# ThermoBase.net
KiCad netlist of a schematic drawn in EAGLE
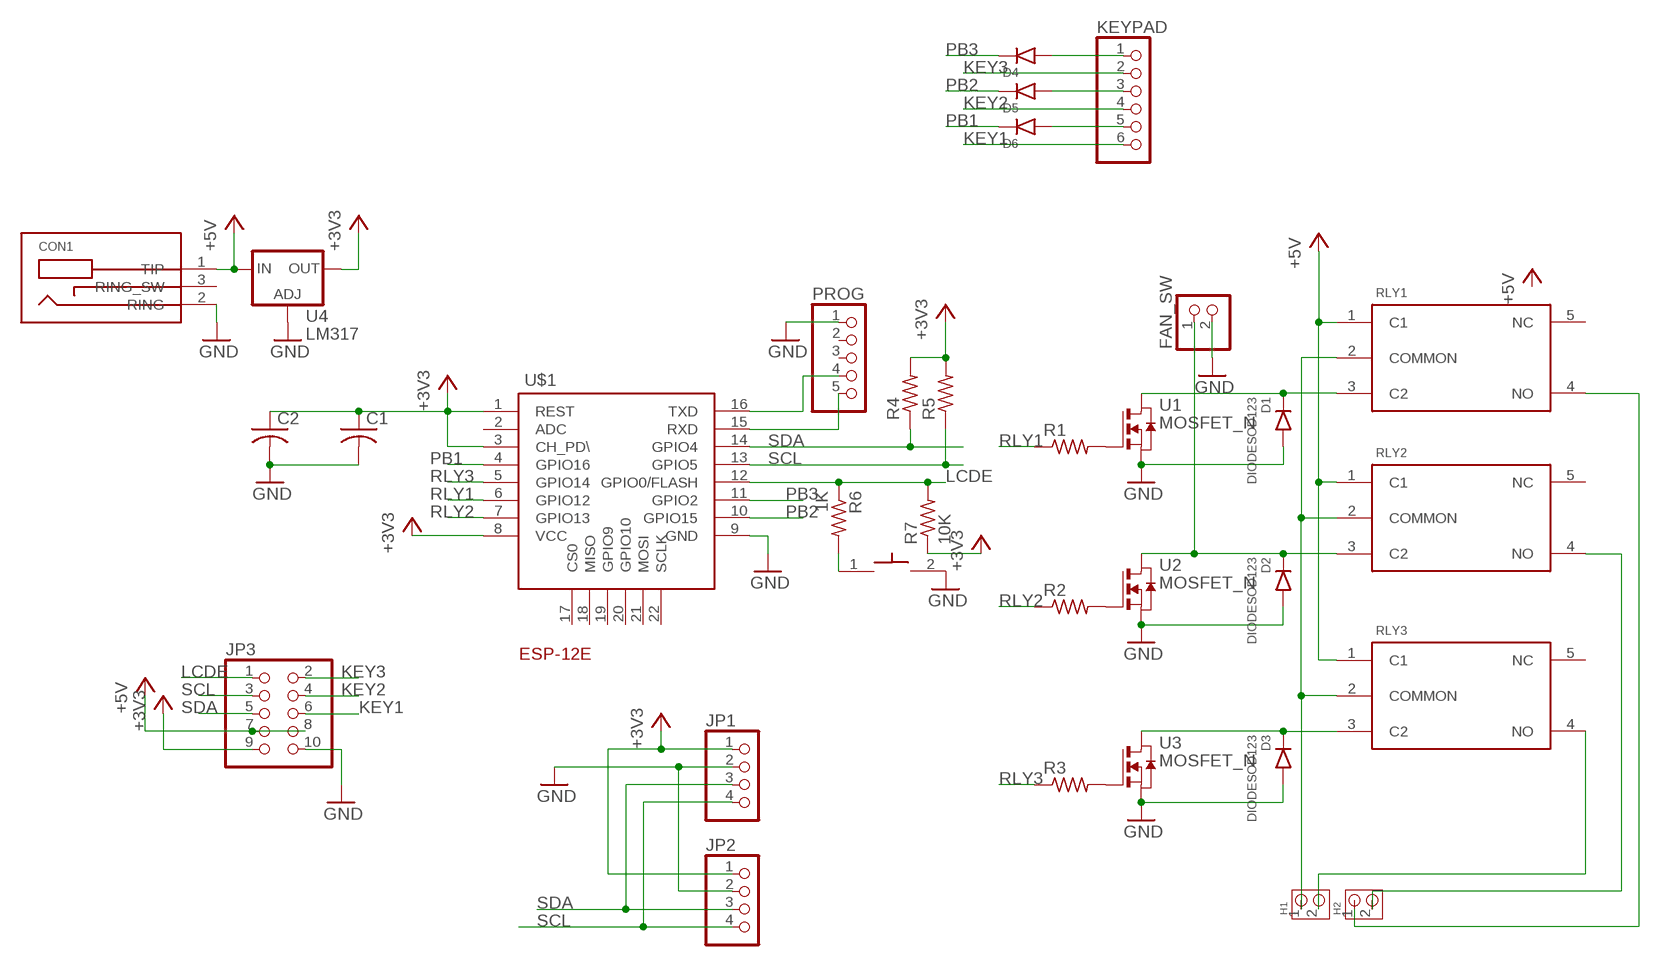
[diagram p0: schematic, sheet 1]

(export (version "E")
  (design (tool "Eeschema 10.0.6"))
  (components
    (comp (ref "BTN1")
      (value "FSMSM_SWITCH_6X3.6")
      (footprint "eagle-import:SMD-2-SWITCH")
      (libsource (lib "eagle-import") (part "FSMSM_SWITCH_6X3.6"))
    )
    (comp (ref "C1")
      (value "C-USC0805")
      (footprint "eagle-import:C0805")
      (libsource (lib "eagle-import") (part "C-USC0805"))
    )
    (comp (ref "C2")
      (value "C-USC0805")
      (footprint "eagle-import:C0805")
      (libsource (lib "eagle-import") (part "C-USC0805"))
    )
    (comp (ref "CON1")
      (value "BARREL_JACK_3PINPJ-102A_2MM_HOLES")
      (footprint "eagle-import:PJ-102A_2MM_HOLES")
      (libsource (lib "eagle-import") (part "BARREL_JACK_3PINPJ-102A_2MM_HOLES"))
    )
    (comp (ref "D1")
      (value "DIODESOD123")
      (footprint "eagle-import:SOD123")
      (libsource (lib "eagle-import") (part "DIODESOD123"))
    )
    (comp (ref "D2")
      (value "DIODESOD123")
      (footprint "eagle-import:SOD123")
      (libsource (lib "eagle-import") (part "DIODESOD123"))
    )
    (comp (ref "D3")
      (value "DIODESOD123")
      (footprint "eagle-import:SOD123")
      (libsource (lib "eagle-import") (part "DIODESOD123"))
    )
    (comp (ref "D4")
      (value "DIODESOD123")
      (footprint "eagle-import:SOD123")
      (libsource (lib "eagle-import") (part "DIODESOD123"))
    )
    (comp (ref "D5")
      (value "DIODESOD123")
      (footprint "eagle-import:SOD123")
      (libsource (lib "eagle-import") (part "DIODESOD123"))
    )
    (comp (ref "D6")
      (value "DIODESOD123")
      (footprint "eagle-import:SOD123")
      (libsource (lib "eagle-import") (part "DIODESOD123"))
    )
    (comp (ref "FAN_SW")
      (value "PINHD-1X2")
      (footprint "eagle-import:1X02")
      (libsource (lib "eagle-import") (part "PINHD-1X2"))
    )
    (comp (ref "H1")
      (value "TERMBLOCK_5MM_2POS")
      (footprint "eagle-import:TERMBLOCK_5MM_2POS")
      (libsource (lib "eagle-import") (part "TERMBLOCK_5MM_2POS"))
    )
    (comp (ref "H2")
      (value "TERMBLOCK_5MM_2POS")
      (footprint "eagle-import:TERMBLOCK_5MM_2POS")
      (libsource (lib "eagle-import") (part "TERMBLOCK_5MM_2POS"))
    )
    (comp (ref "JP1")
      (value "PINHD-1X4")
      (footprint "eagle-import:1X04")
      (libsource (lib "eagle-import") (part "PINHD-1X4"))
    )
    (comp (ref "JP2")
      (value "PINHD-1X4")
      (footprint "eagle-import:1X04")
      (libsource (lib "eagle-import") (part "PINHD-1X4"))
    )
    (comp (ref "JP3")
      (value "PINHD-2X5")
      (footprint "eagle-import:2X05")
      (libsource (lib "eagle-import") (part "PINHD-2X5"))
    )
    (comp (ref "KEYPAD")
      (value "PINHD-1X6")
      (footprint "eagle-import:1X06")
      (libsource (lib "eagle-import") (part "PINHD-1X6"))
    )
    (comp (ref "PROG")
      (value "PINHD-1X5")
      (footprint "eagle-import:1X05")
      (libsource (lib "eagle-import") (part "PINHD-1X5"))
    )
    (comp (ref "R1")
      (value "R-US_R0805")
      (footprint "eagle-import:R0805")
      (libsource (lib "eagle-import") (part "R-US_R0805"))
    )
    (comp (ref "R2")
      (value "R-US_R0805")
      (footprint "eagle-import:R0805")
      (libsource (lib "eagle-import") (part "R-US_R0805"))
    )
    (comp (ref "R3")
      (value "R-US_R0805")
      (footprint "eagle-import:R0805")
      (libsource (lib "eagle-import") (part "R-US_R0805"))
    )
    (comp (ref "R4")
      (value "R-US_R0805")
      (footprint "eagle-import:R0805")
      (libsource (lib "eagle-import") (part "R-US_R0805"))
    )
    (comp (ref "R5")
      (value "R-US_R0805")
      (footprint "eagle-import:R0805")
      (libsource (lib "eagle-import") (part "R-US_R0805"))
    )
    (comp (ref "R6")
      (value "1K")
      (footprint "eagle-import:R0805")
      (libsource (lib "eagle-import") (part "R-US_R0805"))
    )
    (comp (ref "R7")
      (value "10K")
      (footprint "eagle-import:R0805")
      (libsource (lib "eagle-import") (part "R-US_R0805"))
    )
    (comp (ref "RLY1")
      (value "RELAY_JQC-3F")
      (footprint "eagle-import:T73_RELAY")
      (libsource (lib "eagle-import") (part "RELAY_JQC-3F"))
    )
    (comp (ref "RLY2")
      (value "RELAY_JQC-3F")
      (footprint "eagle-import:T73_RELAY")
      (libsource (lib "eagle-import") (part "RELAY_JQC-3F"))
    )
    (comp (ref "RLY3")
      (value "RELAY_JQC-3F")
      (footprint "eagle-import:T73_RELAY")
      (libsource (lib "eagle-import") (part "RELAY_JQC-3F"))
    )
    (comp (ref "U$1")
      (value "ESP-12E")
      (footprint "eagle-import:ESP-12E")
      (libsource (lib "eagle-import") (part "ESP-12E"))
    )
    (comp (ref "U1")
      (value "MOSFET_N")
      (footprint "eagle-import:SOT-23")
      (libsource (lib "eagle-import") (part "MOSFET_N"))
    )
    (comp (ref "U2")
      (value "MOSFET_N")
      (footprint "eagle-import:SOT-23")
      (libsource (lib "eagle-import") (part "MOSFET_N"))
    )
    (comp (ref "U3")
      (value "MOSFET_N")
      (footprint "eagle-import:SOT-23")
      (libsource (lib "eagle-import") (part "MOSFET_N"))
    )
    (comp (ref "U4")
      (value "LM317")
      (footprint "eagle-import:SOT223")
      (libsource (lib "eagle-import") (part "LM317"))
    )
  )
  (nets
    (net (code "1") (name "+3V3") (class "Default")
      (node (ref "C1") (pin "1") (pinfunction "1_1") (pintype "passive"))
      (node (ref "C2") (pin "1") (pinfunction "1_1") (pintype "passive"))
      (node (ref "JP1") (pin "1") (pinfunction "1_1") (pintype "passive"))
      (node (ref "JP2") (pin "1") (pinfunction "1_1") (pintype "passive"))
      (node (ref "JP3") (pin "9") (pinfunction "9_9") (pintype "passive"))
      (node (ref "R4") (pin "2") (pinfunction "2_2") (pintype "passive"))
      (node (ref "R5") (pin "2") (pinfunction "2_2") (pintype "passive"))
      (node (ref "R7") (pin "1") (pinfunction "1_1") (pintype "passive"))
      (node (ref "U$1") (pin "1") (pinfunction "REST_1") (pintype "bidirectional"))
      (node (ref "U$1") (pin "3") (pinfunction "CH_PD\\_3") (pintype "bidirectional"))
      (node (ref "U$1") (pin "8") (pinfunction "VCC_8") (pintype "bidirectional"))
      (node (ref "U4") (pin "2") (pinfunction "OUT_2") (pintype "passive"))
      (node (ref "U4") (pin "4") (pinfunction "OUT_4") (pintype "passive"))
    )
    (net (code "2") (name "+5V") (class "Default")
      (node (ref "CON1") (pin "1") (pinfunction "TIP_1") (pintype "bidirectional"))
      (node (ref "JP3") (pin "7") (pinfunction "7_7") (pintype "passive"))
      (node (ref "JP3") (pin "8") (pinfunction "8_8") (pintype "passive"))
      (node (ref "RLY1") (pin "1") (pinfunction "C1_1") (pintype "bidirectional"))
      (node (ref "RLY2") (pin "1") (pinfunction "C1_1") (pintype "bidirectional"))
      (node (ref "RLY3") (pin "1") (pinfunction "C1_1") (pintype "bidirectional"))
      (node (ref "U4") (pin "3") (pinfunction "IN_3") (pintype "input"))
    )
    (net (code "3") (name "/KEY1") (class "Default")
      (node (ref "JP3") (pin "6") (pinfunction "6_6") (pintype "passive"))
      (node (ref "KEYPAD") (pin "6") (pinfunction "6_6") (pintype "passive"))
    )
    (net (code "4") (name "/KEY2") (class "Default")
      (node (ref "JP3") (pin "4") (pinfunction "4_4") (pintype "passive"))
      (node (ref "KEYPAD") (pin "4") (pinfunction "4_4") (pintype "passive"))
    )
    (net (code "5") (name "/KEY3") (class "Default")
      (node (ref "JP3") (pin "2") (pinfunction "2_2") (pintype "passive"))
      (node (ref "KEYPAD") (pin "2") (pinfunction "2_2") (pintype "passive"))
    )
    (net (code "6") (name "/LCDE") (class "Default")
      (node (ref "JP3") (pin "1") (pinfunction "1_1") (pintype "passive"))
      (node (ref "R6") (pin "1") (pinfunction "1_1") (pintype "passive"))
      (node (ref "R7") (pin "2") (pinfunction "2_2") (pintype "passive"))
      (node (ref "U$1") (pin "12") (pinfunction "GPIO0/FLASH_12") (pintype "bidirectional"))
    )
    (net (code "7") (name "/PB1") (class "Default")
      (node (ref "D6") (pin "2") (pinfunction "C_2") (pintype "bidirectional"))
      (node (ref "U$1") (pin "4") (pinfunction "GPIO16_4") (pintype "bidirectional"))
    )
    (net (code "8") (name "/PB2") (class "Default")
      (node (ref "D5") (pin "2") (pinfunction "C_2") (pintype "bidirectional"))
      (node (ref "U$1") (pin "10") (pinfunction "GPIO15_10") (pintype "bidirectional"))
    )
    (net (code "9") (name "/PB3") (class "Default")
      (node (ref "D4") (pin "2") (pinfunction "C_2") (pintype "bidirectional"))
      (node (ref "U$1") (pin "11") (pinfunction "GPIO2_11") (pintype "bidirectional"))
    )
    (net (code "10") (name "/RLY1") (class "Default")
      (node (ref "R1") (pin "1") (pinfunction "1_1") (pintype "passive"))
      (node (ref "U$1") (pin "6") (pinfunction "GPIO12_6") (pintype "bidirectional"))
    )
    (net (code "11") (name "/RLY2") (class "Default")
      (node (ref "R2") (pin "1") (pinfunction "1_1") (pintype "passive"))
      (node (ref "U$1") (pin "7") (pinfunction "GPIO13_7") (pintype "bidirectional"))
    )
    (net (code "12") (name "/RLY3") (class "Default")
      (node (ref "R3") (pin "1") (pinfunction "1_1") (pintype "passive"))
      (node (ref "U$1") (pin "5") (pinfunction "GPIO14_5") (pintype "bidirectional"))
    )
    (net (code "13") (name "/SCL") (class "Default")
      (node (ref "JP1") (pin "4") (pinfunction "4_4") (pintype "passive"))
      (node (ref "JP2") (pin "4") (pinfunction "4_4") (pintype "passive"))
      (node (ref "JP3") (pin "3") (pinfunction "3_3") (pintype "passive"))
      (node (ref "R5") (pin "1") (pinfunction "1_1") (pintype "passive"))
      (node (ref "U$1") (pin "13") (pinfunction "GPIO5_13") (pintype "bidirectional"))
    )
    (net (code "14") (name "/SDA") (class "Default")
      (node (ref "JP1") (pin "3") (pinfunction "3_3") (pintype "passive"))
      (node (ref "JP2") (pin "3") (pinfunction "3_3") (pintype "passive"))
      (node (ref "JP3") (pin "5") (pinfunction "5_5") (pintype "passive"))
      (node (ref "R4") (pin "1") (pinfunction "1_1") (pintype "passive"))
      (node (ref "U$1") (pin "14") (pinfunction "GPIO4_14") (pintype "bidirectional"))
    )
    (net (code "15") (name "GND") (class "Default")
      (node (ref "BTN1") (pin "2") (pinfunction "P$2_2") (pintype "bidirectional"))
      (node (ref "C1") (pin "2") (pinfunction "2_2") (pintype "passive"))
      (node (ref "C2") (pin "2") (pinfunction "2_2") (pintype "passive"))
      (node (ref "CON1") (pin "2") (pinfunction "RING_2") (pintype "bidirectional"))
      (node (ref "D1") (pin "1") (pinfunction "A_1") (pintype "bidirectional"))
      (node (ref "D2") (pin "1") (pinfunction "A_1") (pintype "bidirectional"))
      (node (ref "D3") (pin "1") (pinfunction "A_1") (pintype "bidirectional"))
      (node (ref "FAN_SW") (pin "2") (pinfunction "2_2") (pintype "passive"))
      (node (ref "JP1") (pin "2") (pinfunction "2_2") (pintype "passive"))
      (node (ref "JP2") (pin "2") (pinfunction "2_2") (pintype "passive"))
      (node (ref "JP3") (pin "10") (pinfunction "10_10") (pintype "passive"))
      (node (ref "PROG") (pin "1") (pinfunction "1_1") (pintype "passive"))
      (node (ref "U$1") (pin "9") (pinfunction "GND_9") (pintype "bidirectional"))
      (node (ref "U1") (pin "2") (pinfunction "S_2") (pintype "passive"))
      (node (ref "U2") (pin "2") (pinfunction "S_2") (pintype "passive"))
      (node (ref "U3") (pin "2") (pinfunction "S_2") (pintype "passive"))
      (node (ref "U4") (pin "1") (pinfunction "ADJ_1") (pintype "input"))
    )
    (net (code "16") (name "Net-(BTN1-P$1)") (class "Default")
      (node (ref "BTN1") (pin "1") (pinfunction "P$1_1") (pintype "bidirectional"))
      (node (ref "R6") (pin "2") (pinfunction "2_2") (pintype "passive"))
    )
    (net (code "17") (name "Net-(D1-C)") (class "Default")
      (node (ref "D1") (pin "2") (pinfunction "C_2") (pintype "bidirectional"))
      (node (ref "RLY1") (pin "3") (pinfunction "C2_3") (pintype "bidirectional"))
      (node (ref "U1") (pin "3") (pinfunction "D_3") (pintype "passive"))
    )
    (net (code "18") (name "Net-(D2-C)") (class "Default")
      (node (ref "D2") (pin "2") (pinfunction "C_2") (pintype "bidirectional"))
      (node (ref "FAN_SW") (pin "1") (pinfunction "1_1") (pintype "passive"))
      (node (ref "RLY2") (pin "3") (pinfunction "C2_3") (pintype "bidirectional"))
      (node (ref "U2") (pin "3") (pinfunction "D_3") (pintype "passive"))
    )
    (net (code "19") (name "Net-(D3-C)") (class "Default")
      (node (ref "D3") (pin "2") (pinfunction "C_2") (pintype "bidirectional"))
      (node (ref "RLY3") (pin "3") (pinfunction "C2_3") (pintype "bidirectional"))
      (node (ref "U3") (pin "3") (pinfunction "D_3") (pintype "passive"))
    )
    (net (code "20") (name "Net-(D4-A)") (class "Default")
      (node (ref "D4") (pin "1") (pinfunction "A_1") (pintype "bidirectional"))
      (node (ref "KEYPAD") (pin "1") (pinfunction "1_1") (pintype "passive"))
    )
    (net (code "21") (name "Net-(D5-A)") (class "Default")
      (node (ref "D5") (pin "1") (pinfunction "A_1") (pintype "bidirectional"))
      (node (ref "KEYPAD") (pin "3") (pinfunction "3_3") (pintype "passive"))
    )
    (net (code "22") (name "Net-(D6-A)") (class "Default")
      (node (ref "D6") (pin "1") (pinfunction "A_1") (pintype "bidirectional"))
      (node (ref "KEYPAD") (pin "5") (pinfunction "5_5") (pintype "passive"))
    )
    (net (code "23") (name "Net-(RLY1-COMMON)") (class "Default")
      (node (ref "H1") (pin "1") (pinfunction "1_1") (pintype "bidirectional"))
      (node (ref "RLY1") (pin "2") (pinfunction "COMMON_2") (pintype "bidirectional"))
      (node (ref "RLY2") (pin "2") (pinfunction "COMMON_2") (pintype "bidirectional"))
      (node (ref "RLY3") (pin "2") (pinfunction "COMMON_2") (pintype "bidirectional"))
    )
    (net (code "24") (name "Net-(RLY1-NO)") (class "Default")
      (node (ref "H2") (pin "1") (pinfunction "1_1") (pintype "bidirectional"))
      (node (ref "RLY1") (pin "4") (pinfunction "NO_4") (pintype "bidirectional"))
    )
    (net (code "25") (name "Net-(RLY2-NO)") (class "Default")
      (node (ref "H2") (pin "2") (pinfunction "2_2") (pintype "bidirectional"))
      (node (ref "RLY2") (pin "4") (pinfunction "NO_4") (pintype "bidirectional"))
    )
    (net (code "26") (name "Net-(RLY3-NO)") (class "Default")
      (node (ref "H1") (pin "2") (pinfunction "2_2") (pintype "bidirectional"))
      (node (ref "RLY3") (pin "4") (pinfunction "NO_4") (pintype "bidirectional"))
    )
    (net (code "27") (name "Net-(U$1-RXD)") (class "Default")
      (node (ref "PROG") (pin "5") (pinfunction "5_5") (pintype "passive"))
      (node (ref "U$1") (pin "15") (pinfunction "RXD_15") (pintype "bidirectional"))
    )
    (net (code "28") (name "Net-(U$1-TXD)") (class "Default")
      (node (ref "PROG") (pin "4") (pinfunction "4_4") (pintype "passive"))
      (node (ref "U$1") (pin "16") (pinfunction "TXD_16") (pintype "bidirectional"))
    )
    (net (code "29") (name "Net-(U1-G)") (class "Default")
      (node (ref "R1") (pin "2") (pinfunction "2_2") (pintype "passive"))
      (node (ref "U1") (pin "1") (pinfunction "G_1") (pintype "passive"))
    )
    (net (code "30") (name "Net-(U2-G)") (class "Default")
      (node (ref "R2") (pin "2") (pinfunction "2_2") (pintype "passive"))
      (node (ref "U2") (pin "1") (pinfunction "G_1") (pintype "passive"))
    )
    (net (code "31") (name "Net-(U3-G)") (class "Default")
      (node (ref "R3") (pin "2") (pinfunction "2_2") (pintype "passive"))
      (node (ref "U3") (pin "1") (pinfunction "G_1") (pintype "passive"))
    )
    (net (code "32") (name "unconnected-(CON1-RING_SW-Pad3)") (class "Default")
      (node (ref "CON1") (pin "3") (pinfunction "RING_SW_3") (pintype "bidirectional"))
    )
    (net (code "33") (name "unconnected-(PROG-Pad2)") (class "Default")
      (node (ref "PROG") (pin "2") (pinfunction "2_2") (pintype "passive"))
    )
    (net (code "34") (name "unconnected-(PROG-Pad3)") (class "Default")
      (node (ref "PROG") (pin "3") (pinfunction "3_3") (pintype "passive"))
    )
    (net (code "35") (name "unconnected-(RLY1-NC-Pad5)") (class "Default")
      (node (ref "RLY1") (pin "5") (pinfunction "NC_5") (pintype "bidirectional"))
    )
    (net (code "36") (name "unconnected-(RLY2-NC-Pad5)") (class "Default")
      (node (ref "RLY2") (pin "5") (pinfunction "NC_5") (pintype "bidirectional"))
    )
    (net (code "37") (name "unconnected-(RLY3-NC-Pad5)") (class "Default")
      (node (ref "RLY3") (pin "5") (pinfunction "NC_5") (pintype "bidirectional"))
    )
    (net (code "38") (name "unconnected-(U$1-ADC-Pad2)") (class "Default")
      (node (ref "U$1") (pin "2") (pinfunction "ADC_2") (pintype "bidirectional"))
    )
    (net (code "39") (name "unconnected-(U$1-CS0-Pad17)") (class "Default")
      (node (ref "U$1") (pin "17") (pinfunction "CS0_17") (pintype "bidirectional"))
    )
    (net (code "40") (name "unconnected-(U$1-GPIO9-Pad19)") (class "Default")
      (node (ref "U$1") (pin "19") (pinfunction "GPIO9_19") (pintype "bidirectional"))
    )
    (net (code "41") (name "unconnected-(U$1-GPIO10-Pad20)") (class "Default")
      (node (ref "U$1") (pin "20") (pinfunction "GPIO10_20") (pintype "bidirectional"))
    )
    (net (code "42") (name "unconnected-(U$1-MISO-Pad18)") (class "Default")
      (node (ref "U$1") (pin "18") (pinfunction "MISO_18") (pintype "bidirectional"))
    )
    (net (code "43") (name "unconnected-(U$1-MOSI-Pad21)") (class "Default")
      (node (ref "U$1") (pin "21") (pinfunction "MOSI_21") (pintype "bidirectional"))
    )
    (net (code "44") (name "unconnected-(U$1-SCLK-Pad22)") (class "Default")
      (node (ref "U$1") (pin "22") (pinfunction "SCLK_22") (pintype "bidirectional"))
    )
  )
)
